# Power.net
KiCad netlist of a schematic drawn in Altium Designer
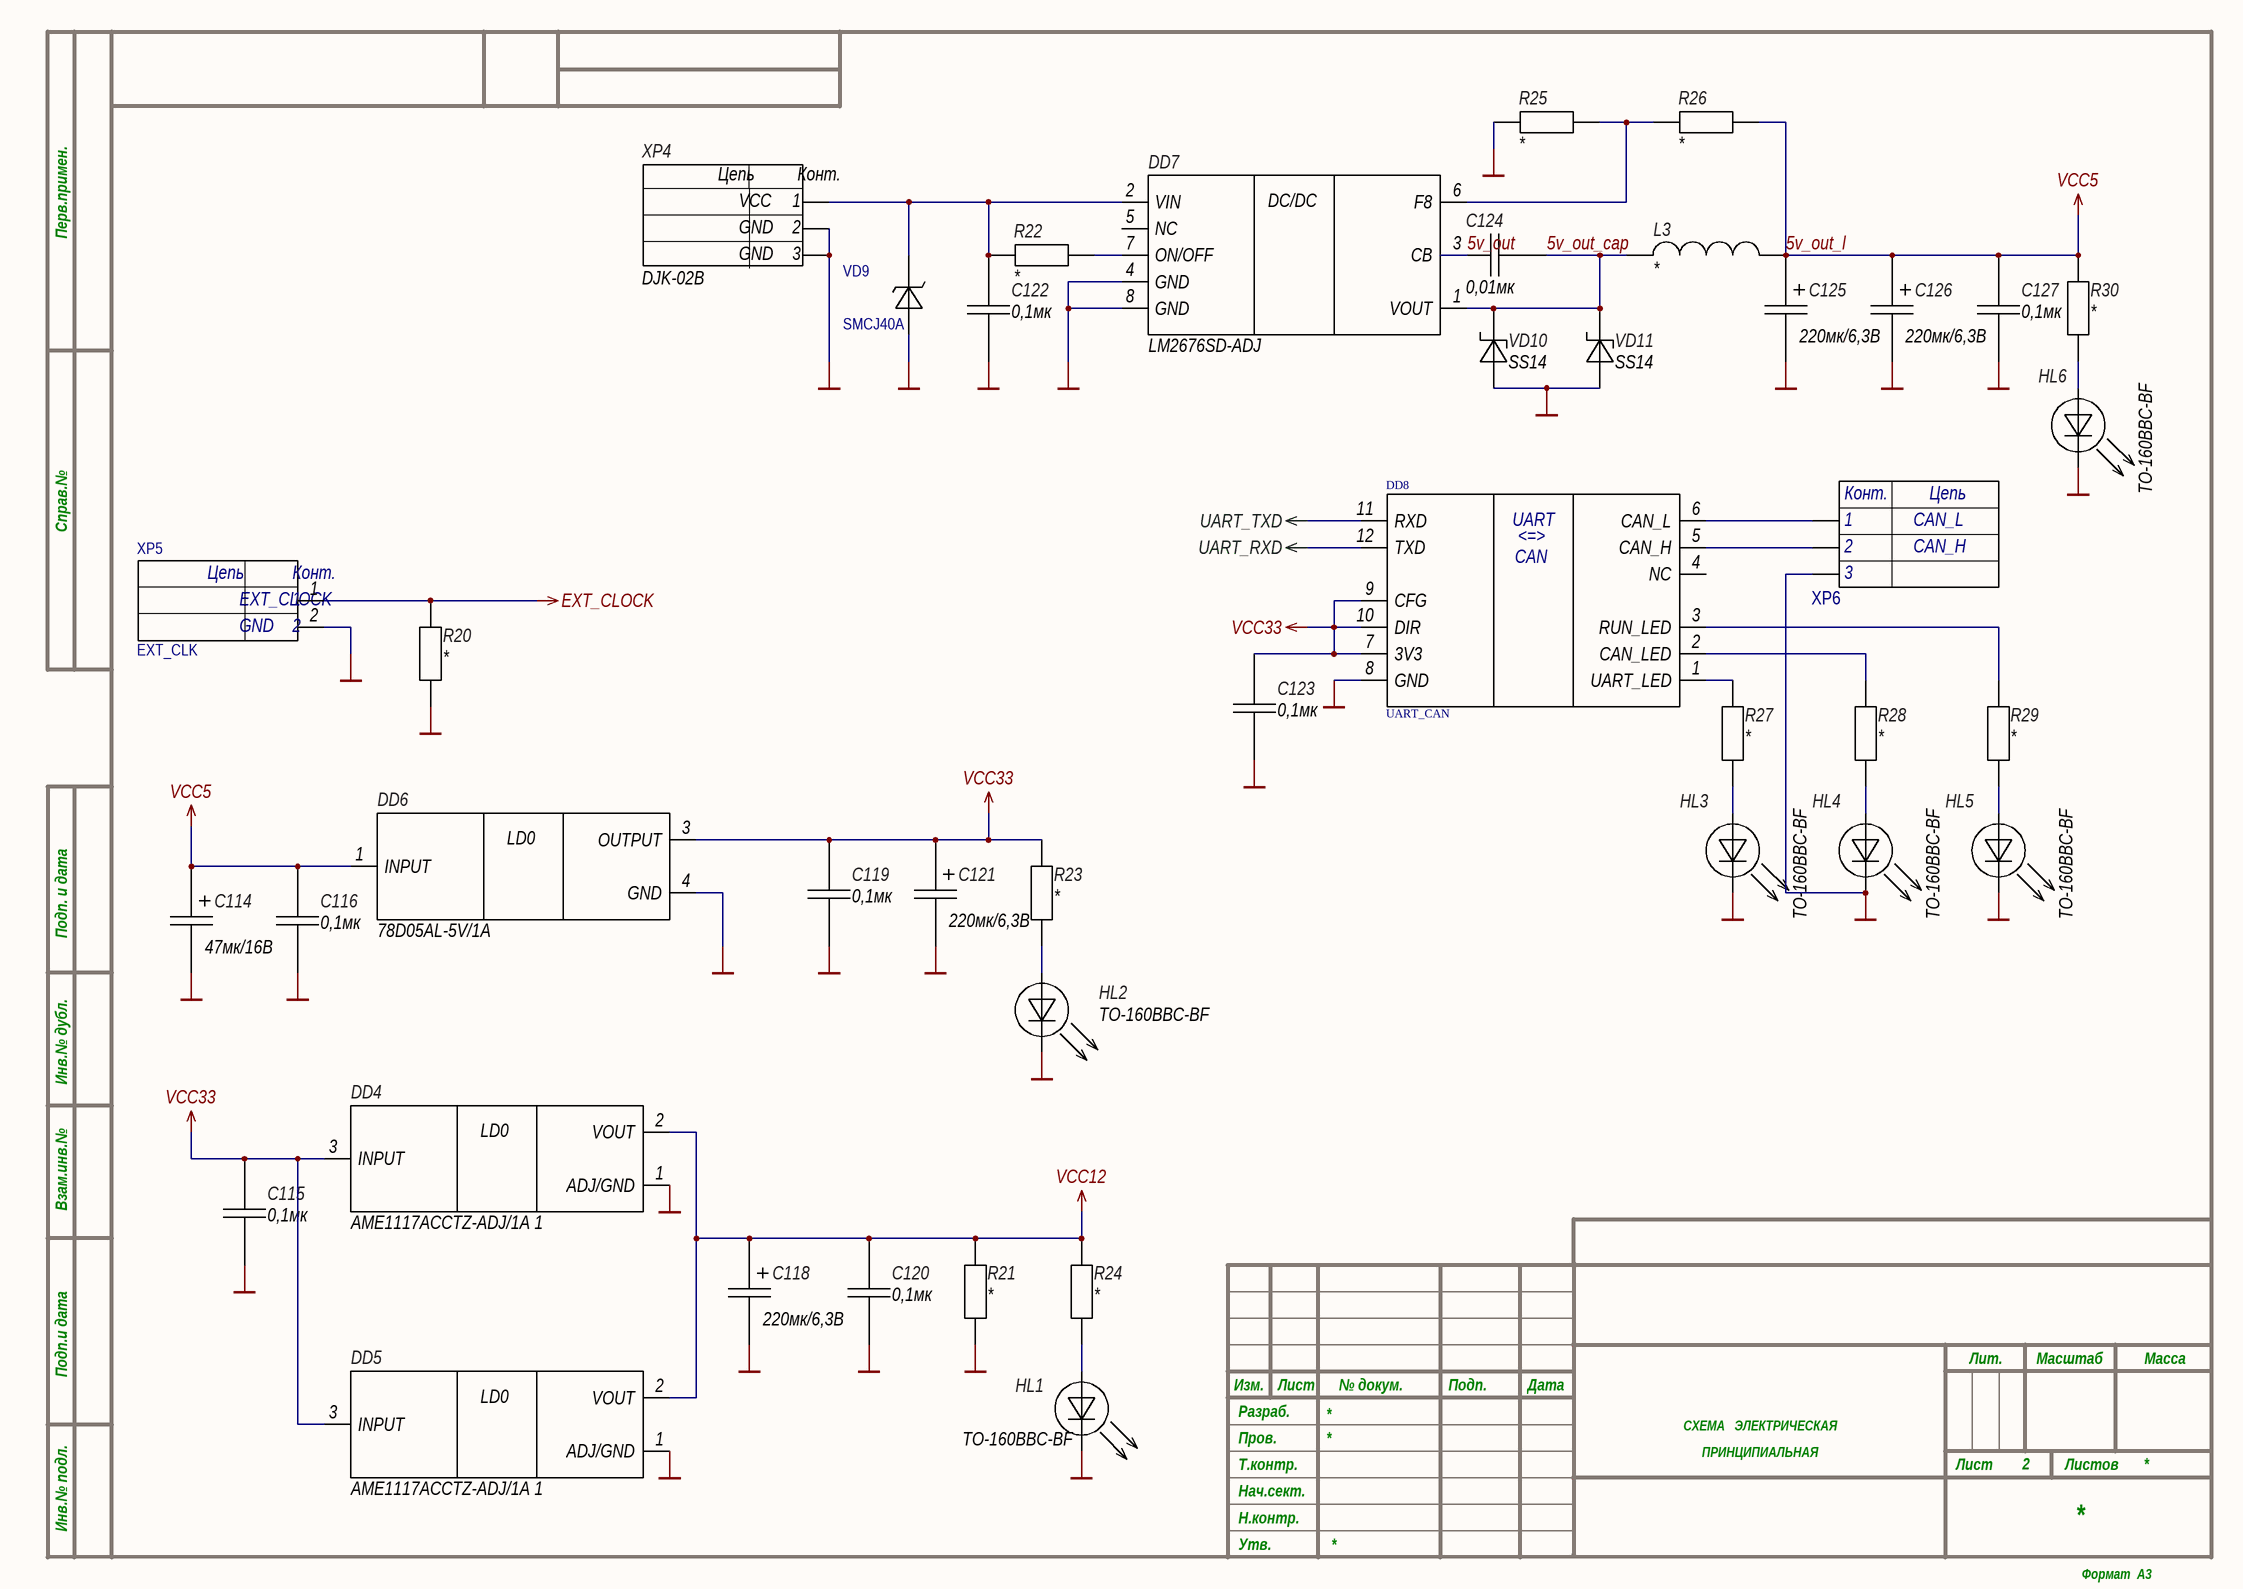
[diagram p0: Power.SchDoc]

(export (version "E")
  (design (tool "Eeschema 10.0.6"))
  (components
    (comp (ref "C114")
      (value "47мк/16B")
      (footprint "CAPAE530X610N")
      (libsource (lib "FPGA_Automotibe_Radar_Lib") (part "Capacitor_pol_47u/16V"))
    )
    (comp (ref "C115")
      (value "0,1мк")
      (footprint "0603")
      (libsource (lib "FPGA_Automotibe_Radar_Lib") (part "Capacitor_0603"))
    )
    (comp (ref "C116")
      (value "0,1мк")
      (footprint "0603")
      (libsource (lib "FPGA_Automotibe_Radar_Lib") (part "Capacitor_0603"))
    )
    (comp (ref "C118")
      (value "220мк/6,3В")
      (footprint "CAPAE530X610N")
      (libsource (lib "FPGA_Automotibe_Radar_Lib") (part "Capacitor_pol_220u/6.3V"))
    )
    (comp (ref "C119")
      (value "0,1мк")
      (footprint "0603")
      (libsource (lib "FPGA_Automotibe_Radar_Lib") (part "Capacitor_0603"))
    )
    (comp (ref "C120")
      (value "0,1мк")
      (footprint "0603")
      (libsource (lib "FPGA_Automotibe_Radar_Lib") (part "Capacitor_0603"))
    )
    (comp (ref "C121")
      (value "220мк/6,3В")
      (footprint "CAPAE530X610N")
      (libsource (lib "FPGA_Automotibe_Radar_Lib") (part "Capacitor_pol_220u/6.3V"))
    )
    (comp (ref "C122")
      (value "0,1мк")
      (footprint "RESC1005X35N")
      (libsource (lib "FPGA_Automotibe_Radar_Lib") (part "Capacitor_0.1u"))
    )
    (comp (ref "C123")
      (value "0,1мк")
      (footprint "0603")
      (libsource (lib "FPGA_Automotibe_Radar_Lib") (part "Capacitor_0603"))
    )
    (comp (ref "C124")
      (value "0,01мк")
      (footprint "ECPU1C154MA5")
      (libsource (lib "FPGA_Automotibe_Radar_Lib") (part "Capacitor"))
    )
    (comp (ref "C125")
      (value "220мк/6,3В")
      (footprint "CAPAE530X610N")
      (libsource (lib "FPGA_Automotibe_Radar_Lib") (part "Capacitor_pol_220u/6.3V"))
    )
    (comp (ref "C126")
      (value "220мк/6,3В")
      (footprint "CAPAE530X610N")
      (libsource (lib "FPGA_Automotibe_Radar_Lib") (part "Capacitor_pol_220u/6.3V"))
    )
    (comp (ref "C127")
      (value "0,1мк")
      (footprint "0603")
      (libsource (lib "FPGA_Automotibe_Radar_Lib") (part "Capacitor_0603"))
    )
    (comp (ref "DD4")
      (value "AME1117ACCTZ-ADJ/1A 1")
      (footprint "SOT230P700X180-4N")
      (libsource (lib "FPGA_Automotibe_Radar_Lib") (part "AME1117ACCTZ-ADJ/1A 1"))
    )
    (comp (ref "DD5")
      (value "AME1117ACCTZ-ADJ/1A 1")
      (footprint "SOT230P700X180-4N")
      (libsource (lib "FPGA_Automotibe_Radar_Lib") (part "AME1117ACCTZ-ADJ/1A 1"))
    )
    (comp (ref "DD6")
      (value "78D05AL-5V/1A")
      (footprint "BD750L5FPCE2")
      (libsource (lib "FPGA_Automotibe_Radar_Lib") (part "78D05AL-5V/1A"))
    )
    (comp (ref "DD7")
      (value "LM2676SD-ADJ")
      (footprint "DFN500X600X100-15N")
      (libsource (lib "FPGA_Automotibe_Radar_Lib") (part "LM2676SD-ADJ"))
    )
    (comp (ref "DD8")
      (value "UART_CAN")
      (footprint "UART_CAN")
      (libsource (lib "FPGA_Automotibe_Radar_Lib") (part "UART_CAN"))
    )
    (comp (ref "HL1")
      (value "TO-160BBC-BF")
      (footprint "15412085A9000")
      (fields (field (name "VALUEMANUFACTURERPARTNUMBER") "fyls-0603urc"))
      (libsource (lib "FPGA_Automotibe_Radar_Lib") (part "TO-160BBC-BF"))
    )
    (comp (ref "HL2")
      (value "TO-160BBC-BF")
      (footprint "15412085A9000")
      (fields (field (name "VALUEMANUFACTURERPARTNUMBER") "fyls-0603urc"))
      (libsource (lib "FPGA_Automotibe_Radar_Lib") (part "TO-160BBC-BF"))
    )
    (comp (ref "HL3")
      (value "TO-160BBC-BF")
      (footprint "15412085A9000")
      (fields (field (name "VALUEMANUFACTURERPARTNUMBER") "fyls-0603urc"))
      (libsource (lib "FPGA_Automotibe_Radar_Lib") (part "TO-160BBC-BF"))
    )
    (comp (ref "HL4")
      (value "TO-160BBC-BF")
      (footprint "15412085A9000")
      (fields (field (name "VALUEMANUFACTURERPARTNUMBER") "fyls-0603urc"))
      (libsource (lib "FPGA_Automotibe_Radar_Lib") (part "TO-160BBC-BF"))
    )
    (comp (ref "HL5")
      (value "TO-160BBC-BF")
      (footprint "15412085A9000")
      (fields (field (name "VALUEMANUFACTURERPARTNUMBER") "fyls-0603urc"))
      (libsource (lib "FPGA_Automotibe_Radar_Lib") (part "TO-160BBC-BF"))
    )
    (comp (ref "HL6")
      (value "TO-160BBC-BF")
      (footprint "15412085A9000")
      (fields (field (name "VALUEMANUFACTURERPARTNUMBER") "fyls-0603urc"))
      (libsource (lib "FPGA_Automotibe_Radar_Lib") (part "TO-160BBC-BF"))
    )
    (comp (ref "L3")
      (value "*")
      (footprint "RESC1005X35N")
      (libsource (lib "FPGA_Automotibe_Radar_Lib") (part "Inductor"))
    )
    (comp (ref "R20")
      (value "*")
      (footprint "RESC3216X75N")
      (fields
        (field (name "TOLERANCE") "5%")
        (field (name "POWER") "0,1 Вт")
        (field (name "VALUEMANUFACTURERPARTNUMBER") "RC0603JR-07680RL")
      )
      (libsource (lib "FPGA_Automotibe_Radar_Lib") (part "Resistor"))
    )
    (comp (ref "R21")
      (value "*")
      (footprint "RESC3216X75N")
      (fields
        (field (name "TOLERANCE") "5%")
        (field (name "POWER") "0,1 Вт")
        (field (name "VALUEMANUFACTURERPARTNUMBER") "RC0603JR-07680RL")
      )
      (libsource (lib "FPGA_Automotibe_Radar_Lib") (part "Resistor_0402_1k"))
    )
    (comp (ref "R22")
      (value "*")
      (footprint "RESC3216X75N")
      (fields
        (field (name "TOLERANCE") "5%")
        (field (name "POWER") "0,1 Вт")
        (field (name "VALUEMANUFACTURERPARTNUMBER") "RC0603JR-07680RL")
      )
      (libsource (lib "FPGA_Automotibe_Radar_Lib") (part "Resistor_1206_10k"))
    )
    (comp (ref "R23")
      (value "*")
      (footprint "RESC3216X75N")
      (fields
        (field (name "TOLERANCE") "5%")
        (field (name "POWER") "0,1 Вт")
        (field (name "VALUEMANUFACTURERPARTNUMBER") "RC0603JR-07680RL")
      )
      (libsource (lib "FPGA_Automotibe_Radar_Lib") (part "Resistor_0402_1k"))
    )
    (comp (ref "R24")
      (value "*")
      (footprint "RESC3216X75N")
      (fields
        (field (name "TOLERANCE") "5%")
        (field (name "POWER") "0,1 Вт")
        (field (name "VALUEMANUFACTURERPARTNUMBER") "RC0603JR-07680RL")
      )
      (libsource (lib "FPGA_Automotibe_Radar_Lib") (part "Resistor_0402_1k"))
    )
    (comp (ref "R25")
      (value "*")
      (footprint "RESC3216X75N")
      (fields
        (field (name "TOLERANCE") "5%")
        (field (name "POWER") "0,1 Вт")
        (field (name "VALUEMANUFACTURERPARTNUMBER") "RC0603JR-07680RL")
      )
      (libsource (lib "FPGA_Automotibe_Radar_Lib") (part "Resistor_0402_1k"))
    )
    (comp (ref "R26")
      (value "*")
      (footprint "RESC3216X75N")
      (fields
        (field (name "TOLERANCE") "5%")
        (field (name "POWER") "0,1 Вт")
        (field (name "VALUEMANUFACTURERPARTNUMBER") "RC0603JR-07680RL")
      )
      (libsource (lib "FPGA_Automotibe_Radar_Lib") (part "Resistor_0402_1k"))
    )
    (comp (ref "R27")
      (value "*")
      (footprint "RESC3216X75N")
      (fields
        (field (name "TOLERANCE") "5%")
        (field (name "POWER") "0,1 Вт")
        (field (name "VALUEMANUFACTURERPARTNUMBER") "RC0603JR-07680RL")
      )
      (libsource (lib "FPGA_Automotibe_Radar_Lib") (part "Resistor_0402_1k"))
    )
    (comp (ref "R28")
      (value "*")
      (footprint "RESC3216X75N")
      (fields
        (field (name "TOLERANCE") "5%")
        (field (name "POWER") "0,1 Вт")
        (field (name "VALUEMANUFACTURERPARTNUMBER") "RC0603JR-07680RL")
      )
      (libsource (lib "FPGA_Automotibe_Radar_Lib") (part "Resistor_0402_1k"))
    )
    (comp (ref "R29")
      (value "*")
      (footprint "RESC3216X75N")
      (fields
        (field (name "TOLERANCE") "5%")
        (field (name "POWER") "0,1 Вт")
        (field (name "VALUEMANUFACTURERPARTNUMBER") "RC0603JR-07680RL")
      )
      (libsource (lib "FPGA_Automotibe_Radar_Lib") (part "Resistor_0402_1k"))
    )
    (comp (ref "R30")
      (value "*")
      (footprint "RESC3216X75N")
      (fields
        (field (name "TOLERANCE") "5%")
        (field (name "POWER") "0,1 Вт")
        (field (name "VALUEMANUFACTURERPARTNUMBER") "RC0603JR-07680RL")
      )
      (libsource (lib "FPGA_Automotibe_Radar_Lib") (part "Resistor"))
    )
    (comp (ref "VD9") (value "SMCJ40A") (libsource (lib "FPGA_Automotibe_Radar_Lib") (part "TVS diode")))
    (comp (ref "VD10")
      (value "SS14")
      (footprint "DIOM5026X262N")
      (fields (field (name "VALUEMANUFACTURERPARTNUMBER") "SS14-E3/61T"))
      (libsource (lib "FPGA_Automotibe_Radar_Lib") (part "DiodeSch_SS14-E3/61T"))
    )
    (comp (ref "VD11")
      (value "SS14")
      (footprint "DIOM5026X262N")
      (fields (field (name "VALUEMANUFACTURERPARTNUMBER") "SS14-E3/61T"))
      (libsource (lib "FPGA_Automotibe_Radar_Lib") (part "DiodeSch_SS14-E3/61T"))
    )
    (comp (ref "XP4")
      (value "DJK-02B")
      (footprint "DJK-02B")
      (libsource (lib "FPGA_Automotibe_Radar_Lib") (part "DJK-02B_PWR_CON"))
    )
    (comp (ref "XP5")
      (value "EXT_CLK")
      (footprint "IPEX")
      (libsource (lib "FPGA_Automotibe_Radar_Lib") (part "SMA_CLK"))
    )
    (comp (ref "XP6")
      (value "header2")
      (footprint "Header_2_phoenix")
      (libsource (lib "FPGA_Automotibe_Radar_Lib") (part "header2"))
    )
  )
  (nets
    (net (code "1") (name "/5v_out") (class "Default")
      (node (ref "C124") (pin "1") (pinfunction "1_1") (pintype "passive"))
      (node (ref "DD7") (pin "3") (pinfunction "CB_3") (pintype "passive"))
    )
    (net (code "2") (name "/5v_out_cap") (class "Default")
      (node (ref "C124") (pin "2") (pinfunction "2_2") (pintype "passive"))
      (node (ref "DD7") (pin "1") (pinfunction "VOUT_1") (pintype "passive"))
      (node (ref "L3") (pin "1") (pinfunction "1_1") (pintype "passive"))
      (node (ref "VD10") (pin "1") (pinfunction "2_1") (pintype "passive"))
      (node (ref "VD11") (pin "1") (pinfunction "2_1") (pintype "passive"))
    )
    (net (code "3") (name "EXT_CLOCK") (class "Default")
      (node (ref "R20") (pin "2") (pinfunction "2_2") (pintype "passive"))
      (node (ref "XP5") (pin "1") (pinfunction "1_1") (pintype "passive"))
    )
    (net (code "4") (name "GND") (class "Default")
      (node (ref "C114") (pin "2") (pinfunction "2_2") (pintype "passive"))
      (node (ref "C115") (pin "2") (pinfunction "2_2") (pintype "passive"))
      (node (ref "C116") (pin "2") (pinfunction "2_2") (pintype "passive"))
      (node (ref "C118") (pin "2") (pinfunction "2_2") (pintype "passive"))
      (node (ref "C119") (pin "2") (pinfunction "2_2") (pintype "passive"))
      (node (ref "C120") (pin "2") (pinfunction "2_2") (pintype "passive"))
      (node (ref "C121") (pin "2") (pinfunction "2_2") (pintype "passive"))
      (node (ref "C122") (pin "2") (pinfunction "2_2") (pintype "passive"))
      (node (ref "C123") (pin "2") (pinfunction "2_2") (pintype "passive"))
      (node (ref "C125") (pin "2") (pinfunction "2_2") (pintype "passive"))
      (node (ref "C126") (pin "2") (pinfunction "2_2") (pintype "passive"))
      (node (ref "C127") (pin "2") (pinfunction "2_2") (pintype "passive"))
      (node (ref "DD4") (pin "1") (pinfunction "ADJ/GND_1") (pintype "passive"))
      (node (ref "DD5") (pin "1") (pinfunction "ADJ/GND_1") (pintype "passive"))
      (node (ref "DD6") (pin "4") (pinfunction "GND_4") (pintype "passive"))
      (node (ref "DD7") (pin "4") (pinfunction "GND_4") (pintype "passive"))
      (node (ref "DD7") (pin "8") (pinfunction "GND_8") (pintype "passive"))
      (node (ref "DD8") (pin "8") (pinfunction "GND_8") (pintype "passive"))
      (node (ref "HL1") (pin "2") (pinfunction "2_2") (pintype "passive"))
      (node (ref "HL2") (pin "2") (pinfunction "2_2") (pintype "passive"))
      (node (ref "HL3") (pin "2") (pinfunction "2_2") (pintype "passive"))
      (node (ref "HL4") (pin "2") (pinfunction "2_2") (pintype "passive"))
      (node (ref "HL5") (pin "2") (pinfunction "2_2") (pintype "passive"))
      (node (ref "HL6") (pin "2") (pinfunction "2_2") (pintype "passive"))
      (node (ref "R20") (pin "1") (pinfunction "1_1") (pintype "passive"))
      (node (ref "R21") (pin "1") (pinfunction "1_1") (pintype "passive"))
      (node (ref "R25") (pin "1") (pinfunction "1_1") (pintype "passive"))
      (node (ref "VD10") (pin "2") (pinfunction "2_2") (pintype "passive"))
      (node (ref "VD11") (pin "2") (pinfunction "2_2") (pintype "passive"))
      (node (ref "VD9") (pin "A") (pinfunction "2_A") (pintype "passive"))
      (node (ref "XP4") (pin "2") (pinfunction "2_2") (pintype "passive"))
      (node (ref "XP4") (pin "3") (pinfunction "3_3") (pintype "passive"))
      (node (ref "XP5") (pin "2") (pinfunction "2_2") (pintype "passive"))
      (node (ref "XP6") (pin "GND") (pinfunction "GND_GND") (pintype "passive"))
    )
    (net (code "5") (name "Net-(DD7-F8)") (class "Default")
      (node (ref "DD7") (pin "6") (pinfunction "F8_6") (pintype "passive"))
      (node (ref "R25") (pin "2") (pinfunction "2_2") (pintype "passive"))
      (node (ref "R26") (pin "1") (pinfunction "1_1") (pintype "passive"))
    )
    (net (code "6") (name "Net-(DD7-ON{slash}OFF)") (class "Default")
      (node (ref "DD7") (pin "7") (pinfunction "ON/OFF_7") (pintype "passive"))
      (node (ref "R22") (pin "2") (pinfunction "2_2") (pintype "passive"))
    )
    (net (code "7") (name "Net-(DD7-VIN)") (class "Default")
      (node (ref "C122") (pin "1") (pinfunction "1_1") (pintype "passive"))
      (node (ref "DD7") (pin "2") (pinfunction "VIN_2") (pintype "passive"))
      (node (ref "R22") (pin "1") (pinfunction "1_1") (pintype "passive"))
      (node (ref "VD9") (pin "1") (pinfunction "2_1") (pintype "passive"))
      (node (ref "XP4") (pin "1") (pinfunction "1_1") (pintype "passive"))
    )
    (net (code "8") (name "Net-(DD8-CAN_H)") (class "Default")
      (node (ref "DD8") (pin "5") (pinfunction "CAN_H_5") (pintype "passive"))
      (node (ref "XP6") (pin "2") (pinfunction "2_2") (pintype "passive"))
    )
    (net (code "9") (name "Net-(DD8-CAN_L)") (class "Default")
      (node (ref "DD8") (pin "6") (pinfunction "CAN_L_6") (pintype "passive"))
      (node (ref "XP6") (pin "1") (pinfunction "1_1") (pintype "passive"))
    )
    (net (code "10") (name "Net-(DD8-CAN_LED)") (class "Default")
      (node (ref "DD8") (pin "2") (pinfunction "CAN_LED_2") (pintype "passive"))
      (node (ref "R28") (pin "2") (pinfunction "2_2") (pintype "passive"))
    )
    (net (code "11") (name "Net-(DD8-RUN_LED)") (class "Default")
      (node (ref "DD8") (pin "3") (pinfunction "RUN_LED_3") (pintype "passive"))
      (node (ref "R29") (pin "2") (pinfunction "2_2") (pintype "passive"))
    )
    (net (code "12") (name "Net-(DD8-UART_LED)") (class "Default")
      (node (ref "DD8") (pin "1") (pinfunction "UART_LED_1") (pintype "passive"))
      (node (ref "R27") (pin "2") (pinfunction "2_2") (pintype "passive"))
    )
    (net (code "13") (name "Net-(HL1-Pad1)") (class "Default")
      (node (ref "HL1") (pin "1") (pinfunction "1_1") (pintype "passive"))
      (node (ref "R24") (pin "1") (pinfunction "1_1") (pintype "passive"))
    )
    (net (code "14") (name "Net-(HL2-Pad1)") (class "Default")
      (node (ref "HL2") (pin "1") (pinfunction "1_1") (pintype "passive"))
      (node (ref "R23") (pin "1") (pinfunction "1_1") (pintype "passive"))
    )
    (net (code "15") (name "Net-(HL3-Pad1)") (class "Default")
      (node (ref "HL3") (pin "1") (pinfunction "1_1") (pintype "passive"))
      (node (ref "R27") (pin "1") (pinfunction "1_1") (pintype "passive"))
    )
    (net (code "16") (name "Net-(HL4-Pad1)") (class "Default")
      (node (ref "HL4") (pin "1") (pinfunction "1_1") (pintype "passive"))
      (node (ref "R28") (pin "1") (pinfunction "1_1") (pintype "passive"))
    )
    (net (code "17") (name "Net-(HL5-Pad1)") (class "Default")
      (node (ref "HL5") (pin "1") (pinfunction "1_1") (pintype "passive"))
      (node (ref "R29") (pin "1") (pinfunction "1_1") (pintype "passive"))
    )
    (net (code "18") (name "Net-(HL6-Pad1)") (class "Default")
      (node (ref "HL6") (pin "1") (pinfunction "1_1") (pintype "passive"))
      (node (ref "R30") (pin "1") (pinfunction "1_1") (pintype "passive"))
    )
    (net (code "19") (name "UART_RXD") (class "Default")
      (node (ref "DD8") (pin "12") (pinfunction "TXD_12") (pintype "passive"))
    )
    (net (code "20") (name "UART_TXD") (class "Default")
      (node (ref "DD8") (pin "11") (pinfunction "RXD_11") (pintype "passive"))
    )
    (net (code "21") (name "VCC5") (class "Default")
      (node (ref "C114") (pin "1") (pinfunction "1_1") (pintype "passive"))
      (node (ref "C116") (pin "1") (pinfunction "1_1") (pintype "passive"))
      (node (ref "C125") (pin "1") (pinfunction "1_1") (pintype "passive"))
      (node (ref "C126") (pin "1") (pinfunction "1_1") (pintype "passive"))
      (node (ref "C127") (pin "1") (pinfunction "1_1") (pintype "passive"))
      (node (ref "DD6") (pin "1") (pinfunction "INPUT_1") (pintype "passive"))
      (node (ref "L3") (pin "2") (pinfunction "2_2") (pintype "passive"))
      (node (ref "R26") (pin "2") (pinfunction "2_2") (pintype "passive"))
      (node (ref "R30") (pin "2") (pinfunction "2_2") (pintype "passive"))
    )
    (net (code "22") (name "VCC12") (class "Default")
      (node (ref "C118") (pin "1") (pinfunction "1_1") (pintype "passive"))
      (node (ref "C120") (pin "1") (pinfunction "1_1") (pintype "passive"))
      (node (ref "DD4") (pin "2") (pinfunction "VOUT_2") (pintype "passive"))
      (node (ref "DD5") (pin "2") (pinfunction "VOUT_2") (pintype "passive"))
      (node (ref "R21") (pin "2") (pinfunction "2_2") (pintype "passive"))
      (node (ref "R24") (pin "2") (pinfunction "2_2") (pintype "passive"))
    )
    (net (code "23") (name "VCC33") (class "Default")
      (node (ref "C115") (pin "1") (pinfunction "1_1") (pintype "passive"))
      (node (ref "C119") (pin "1") (pinfunction "1_1") (pintype "passive"))
      (node (ref "C121") (pin "1") (pinfunction "1_1") (pintype "passive"))
      (node (ref "C123") (pin "1") (pinfunction "1_1") (pintype "passive"))
      (node (ref "DD4") (pin "3") (pinfunction "INPUT_3") (pintype "passive"))
      (node (ref "DD5") (pin "3") (pinfunction "INPUT_3") (pintype "passive"))
      (node (ref "DD6") (pin "3") (pinfunction "OUTPUT_3") (pintype "passive"))
      (node (ref "DD8") (pin "10") (pinfunction "DIR_10") (pintype "passive"))
      (node (ref "DD8") (pin "7") (pinfunction "3V3_7") (pintype "passive"))
      (node (ref "DD8") (pin "9") (pinfunction "CFG_9") (pintype "passive"))
      (node (ref "R23") (pin "2") (pinfunction "2_2") (pintype "passive"))
    )
    (net (code "24") (name "unconnected-(DD7-NC-Pad5)") (class "Default")
      (node (ref "DD7") (pin "5") (pinfunction "NC_5") (pintype "passive"))
    )
    (net (code "25") (name "unconnected-(DD8-NC-Pad4)") (class "Default")
      (node (ref "DD8") (pin "4") (pinfunction "NC_4") (pintype "passive"))
    )
  )
)
